# PowerManagement.net
KiCad netlist of a schematic drawn in Altium Designer
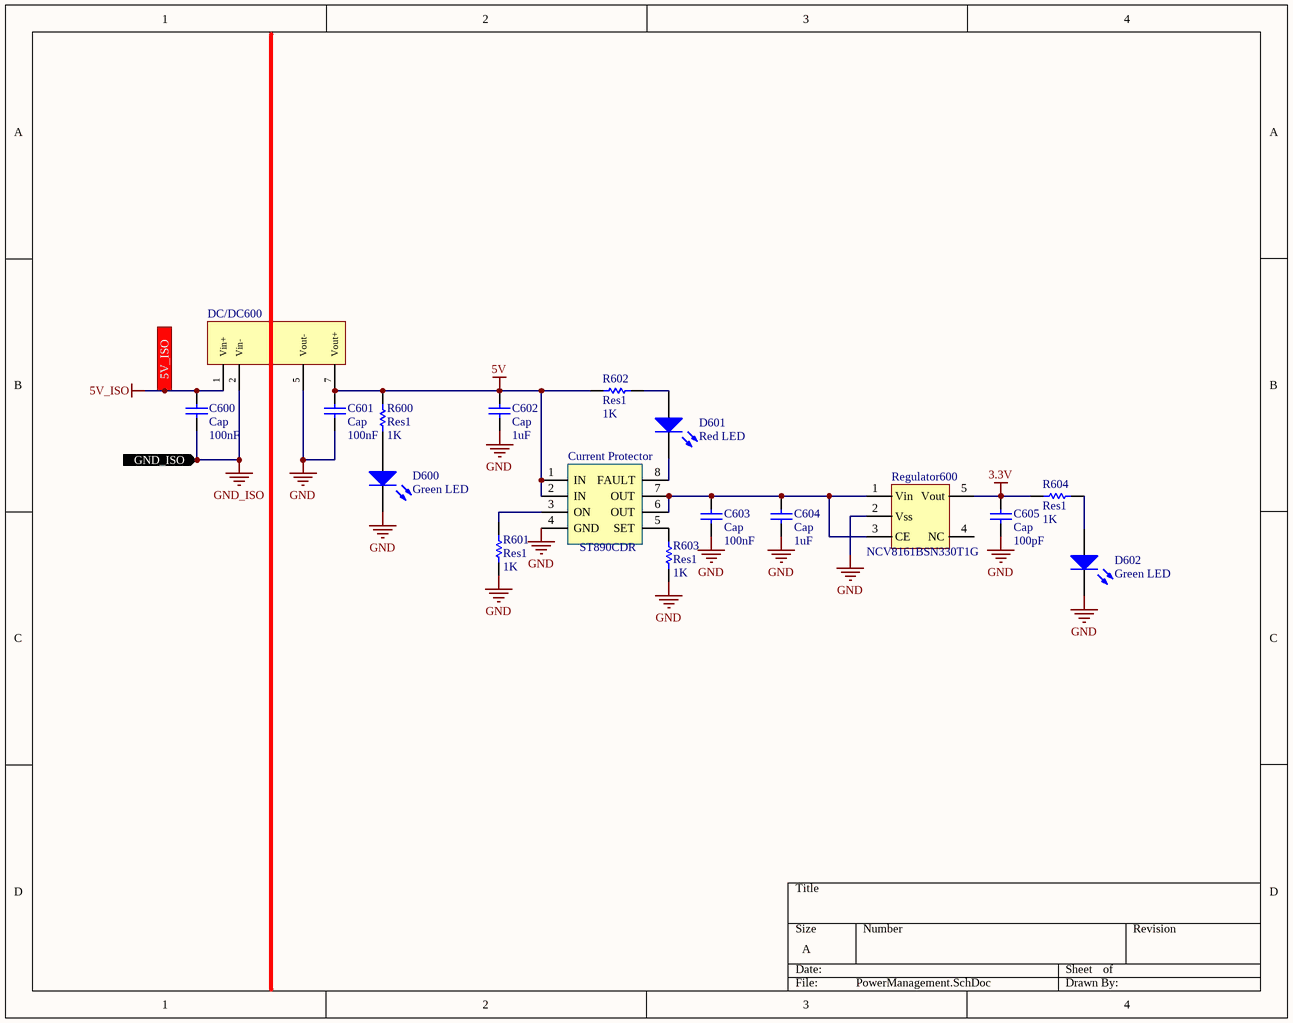
[diagram p0: PowerManagement.SchDoc]

(export (version "E")
  (design (tool "Eeschema 10.0.6"))
  (components
    (comp (ref "C600")
      (value "Cap")
      (footprint "RAD-0.3")
      (description "Capacitor")
      (fields (field (name "ALTIUM_VALUE") "100nF") (field (name "PUBLISHER") "Altium Limited"))
      (libsource (lib "Miscellaneous Devices") (part "Cap"))
    )
    (comp (ref "C601")
      (value "Cap")
      (footprint "RAD-0.3")
      (description "Capacitor")
      (fields (field (name "ALTIUM_VALUE") "100nF") (field (name "PUBLISHER") "Altium Limited"))
      (libsource (lib "Miscellaneous Devices") (part "Cap"))
    )
    (comp (ref "C602")
      (value "Cap")
      (footprint "RAD-0.3")
      (description "Capacitor")
      (fields (field (name "ALTIUM_VALUE") "1uF") (field (name "PUBLISHER") "Altium Limited"))
      (libsource (lib "Miscellaneous Devices") (part "Cap"))
    )
    (comp (ref "C603")
      (value "Cap")
      (footprint "RAD-0.3")
      (description "Capacitor")
      (fields (field (name "ALTIUM_VALUE") "100nF") (field (name "PUBLISHER") "Altium Limited"))
      (libsource (lib "Miscellaneous Devices") (part "Cap"))
    )
    (comp (ref "C604")
      (value "Cap")
      (footprint "RAD-0.3")
      (description "Capacitor")
      (fields (field (name "ALTIUM_VALUE") "1uF") (field (name "PUBLISHER") "Altium Limited"))
      (libsource (lib "Miscellaneous Devices") (part "Cap"))
    )
    (comp (ref "C605")
      (value "Cap")
      (footprint "RAD-0.3")
      (description "Capacitor")
      (fields (field (name "ALTIUM_VALUE") "100pF") (field (name "PUBLISHER") "Altium Limited"))
      (libsource (lib "Miscellaneous Devices") (part "Cap"))
    )
    (comp (ref "Current Protector")
      (value "ST890CDR")
      (footprint "SOIC127P600X175-8N")
      (description "1.2A Current Limited High-Side Power Switch with Thermal Shutdown")
      (libsource (lib "CurrentProtector_ST890CDR") (part "ST890CDR"))
    )
    (comp (ref "D600")
      (value "Green LED")
      (footprint "LED-0")
      (description "Typical INFRARED GaAs LED")
      (fields (field (name "PUBLISHER") "Altium Limited"))
      (libsource (lib "Miscellaneous Devices") (part "LED0"))
    )
    (comp (ref "D601")
      (value "Red LED")
      (footprint "LED-0")
      (description "Typical INFRARED GaAs LED")
      (fields (field (name "PUBLISHER") "Altium Limited"))
      (libsource (lib "Miscellaneous Devices") (part "LED0"))
    )
    (comp (ref "D602")
      (value "Green LED")
      (footprint "LED-0")
      (description "Typical INFRARED GaAs LED")
      (fields (field (name "PUBLISHER") "Altium Limited"))
      (libsource (lib "Miscellaneous Devices") (part "LED0"))
    )
    (comp (ref "DC/DC600")
      (value "Isolated5VDC/DC")
      (footprint "Isolated DC/DC")
      (description "RKZE-0505S/H Isolated DC/DC Converters 2W 05Vin 5Vout 400mA Single SIP7")
      (libsource (lib "Isolated_DCDC_5V") (part "Isolated DC/DC"))
    )
    (comp (ref "R600")
      (value "Res1")
      (footprint "AXIAL-0.3")
      (description "Resistor")
      (fields (field (name "ALTIUM_VALUE") "1K") (field (name "PUBLISHER") "Altium Limited"))
      (libsource (lib "Miscellaneous Devices") (part "Res1"))
    )
    (comp (ref "R601")
      (value "Res1")
      (footprint "AXIAL-0.3")
      (description "Resistor")
      (fields (field (name "ALTIUM_VALUE") "1K") (field (name "PUBLISHER") "Altium Limited"))
      (libsource (lib "Miscellaneous Devices") (part "Res1"))
    )
    (comp (ref "R602")
      (value "Res1")
      (footprint "AXIAL-0.3")
      (description "Resistor")
      (fields (field (name "ALTIUM_VALUE") "1K") (field (name "PUBLISHER") "Altium Limited"))
      (libsource (lib "Miscellaneous Devices") (part "Res1"))
    )
    (comp (ref "R603")
      (value "Res1")
      (footprint "AXIAL-0.3")
      (description "Resistor")
      (fields (field (name "ALTIUM_VALUE") "1K") (field (name "PUBLISHER") "Altium Limited"))
      (libsource (lib "Miscellaneous Devices") (part "Res1"))
    )
    (comp (ref "R604")
      (value "Res1")
      (footprint "AXIAL-0.3")
      (description "Resistor")
      (fields (field (name "ALTIUM_VALUE") "1K") (field (name "PUBLISHER") "Altium Limited"))
      (libsource (lib "Miscellaneous Devices") (part "Res1"))
    )
    (comp (ref "Regulator600")
      (value "NCV8161BSN330T1G")
      (footprint "SOT95P280X110-5N")
      (description "450 mA, Ultra-Low Noise  and High PSRR LDO  Regulator for RF and  Analog Circuits")
      (libsource (lib "Regulator3.3V") (part "NCV8161BSN330T1G"))
    )
  )
  (nets
    (net (code "1") (name "3.3V") (class "Default")
      (node (ref "C605") (pin "1") (pinfunction "1_1") (pintype "passive"))
      (node (ref "R604") (pin "2") (pinfunction "2_2") (pintype "passive"))
      (node (ref "Regulator600") (pin "5") (pinfunction "Vout_5") (pintype "passive"))
    )
    (net (code "2") (name "5V") (class "Default")
      (node (ref "C601") (pin "1") (pinfunction "1_1") (pintype "passive"))
      (node (ref "C602") (pin "2") (pinfunction "2_2") (pintype "passive"))
      (node (ref "Current Protector") (pin "1") (pinfunction "IN_1") (pintype "passive"))
      (node (ref "Current Protector") (pin "2") (pinfunction "IN_2") (pintype "passive"))
      (node (ref "DC/DC600") (pin "7") (pinfunction "Vout+_7") (pintype "passive"))
      (node (ref "R600") (pin "2") (pinfunction "2_2") (pintype "passive"))
      (node (ref "R602") (pin "2") (pinfunction "2_2") (pintype "passive"))
    )
    (net (code "3") (name "5V_ISO") (class "Default")
      (node (ref "C600") (pin "1") (pinfunction "1_1") (pintype "passive"))
      (node (ref "DC/DC600") (pin "1") (pinfunction "Vin+_1") (pintype "passive"))
    )
    (net (code "4") (name "GND") (class "Default")
      (node (ref "C601") (pin "2") (pinfunction "2_2") (pintype "passive"))
      (node (ref "C602") (pin "1") (pinfunction "1_1") (pintype "passive"))
      (node (ref "C603") (pin "2") (pinfunction "2_2") (pintype "passive"))
      (node (ref "C604") (pin "1") (pinfunction "1_1") (pintype "passive"))
      (node (ref "C605") (pin "2") (pinfunction "2_2") (pintype "passive"))
      (node (ref "Current Protector") (pin "4") (pinfunction "GND_4") (pintype "passive"))
      (node (ref "D600") (pin "2") (pinfunction "K_2") (pintype "passive"))
      (node (ref "D602") (pin "2") (pinfunction "K_2") (pintype "passive"))
      (node (ref "DC/DC600") (pin "5") (pinfunction "Vout-_5") (pintype "passive"))
      (node (ref "R601") (pin "1") (pinfunction "1_1") (pintype "passive"))
      (node (ref "R603") (pin "1") (pinfunction "1_1") (pintype "passive"))
      (node (ref "Regulator600") (pin "2") (pinfunction "Vss_2") (pintype "passive"))
    )
    (net (code "5") (name "GND_ISO") (class "Default")
      (node (ref "C600") (pin "2") (pinfunction "2_2") (pintype "passive"))
      (node (ref "DC/DC600") (pin "2") (pinfunction "Vin-_2") (pintype "passive"))
    )
    (net (code "6") (name "Net-(Current Protector-FAULT)") (class "Default")
      (node (ref "Current Protector") (pin "8") (pinfunction "FAULT_8") (pintype "passive"))
      (node (ref "D601") (pin "2") (pinfunction "K_2") (pintype "passive"))
    )
    (net (code "7") (name "Net-(Current Protector-ON)") (class "Default")
      (node (ref "Current Protector") (pin "3") (pinfunction "ON_3") (pintype "passive"))
      (node (ref "R601") (pin "2") (pinfunction "2_2") (pintype "passive"))
    )
    (net (code "8") (name "Net-(Current Protector-SET)") (class "Default")
      (node (ref "Current Protector") (pin "5") (pinfunction "SET_5") (pintype "passive"))
      (node (ref "R603") (pin "2") (pinfunction "2_2") (pintype "passive"))
    )
    (net (code "9") (name "Net-(D600-A)") (class "Default")
      (node (ref "D600") (pin "1") (pinfunction "A_1") (pintype "passive"))
      (node (ref "R600") (pin "1") (pinfunction "1_1") (pintype "passive"))
    )
    (net (code "10") (name "Net-(D601-A)") (class "Default")
      (node (ref "D601") (pin "1") (pinfunction "A_1") (pintype "passive"))
      (node (ref "R602") (pin "1") (pinfunction "1_1") (pintype "passive"))
    )
    (net (code "11") (name "Net-(D602-A)") (class "Default")
      (node (ref "D602") (pin "1") (pinfunction "A_1") (pintype "passive"))
      (node (ref "R604") (pin "1") (pinfunction "1_1") (pintype "passive"))
    )
    (net (code "12") (name "Net-(Regulator600-CE)") (class "Default")
      (node (ref "C603") (pin "1") (pinfunction "1_1") (pintype "passive"))
      (node (ref "C604") (pin "2") (pinfunction "2_2") (pintype "passive"))
      (node (ref "Current Protector") (pin "6") (pinfunction "OUT_6") (pintype "passive"))
      (node (ref "Current Protector") (pin "7") (pinfunction "OUT_7") (pintype "passive"))
      (node (ref "Regulator600") (pin "1") (pinfunction "Vin_1") (pintype "passive"))
      (node (ref "Regulator600") (pin "3") (pinfunction "CE_3") (pintype "passive"))
    )
    (net (code "13") (name "unconnected-(Regulator600-NC-Pad4)") (class "Default")
      (node (ref "Regulator600") (pin "4") (pinfunction "NC_4") (pintype "passive"))
    )
  )
)
